# dps.net
KiCad netlist of a schematic drawn in EAGLE
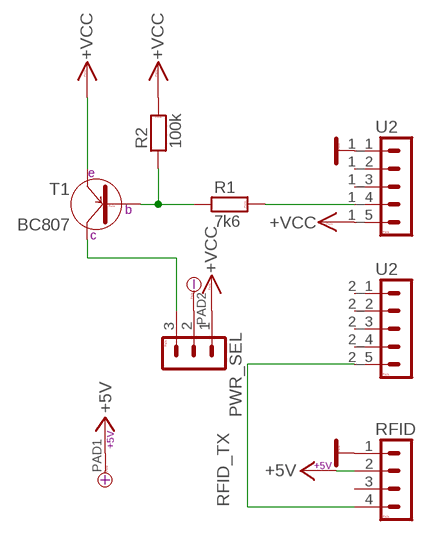
[diagram p0: schematic, sheet 1]

(export (version "E")
  (design (tool "Eeschema 10.0.6"))
  (components
    (comp (ref "PAD1")
      (value "+")
      (footprint "eagle-import:PAD_1")
      (libsource (lib "eagle-import") (part "PAD_1+"))
    )
    (comp (ref "PAD2")
      (value "-")
      (footprint "eagle-import:PAD_1")
      (libsource (lib "eagle-import") (part "PAD_1-"))
    )
    (comp (ref "PWR_SEL")
      (value "S1G3_JUMP")
      (footprint "eagle-import:S1G3_JUM")
      (libsource (lib "eagle-import") (part "S1G3_JUMP"))
    )
    (comp (ref "R1")
      (value "7k6")
      (footprint "eagle-import:1206")
      (libsource (lib "eagle-import") (part "R_SMD_1206"))
    )
    (comp (ref "R2")
      (value "100k")
      (footprint "eagle-import:1206")
      (libsource (lib "eagle-import") (part "R_SMD_1206"))
    )
    (comp (ref "RFID")
      (value "S1G4_JUMP")
      (footprint "eagle-import:S1G4_JUM")
      (libsource (lib "eagle-import") (part "S1G4_JUMP"))
    )
    (comp (ref "T1")
      (value "BC807")
      (footprint "eagle-import:SOT-23")
      (libsource (lib "eagle-import") (part "BC807"))
    )
    (comp (ref "U2")
      (value "S2G5_JUMP")
      (footprint "eagle-import:S2G5_JUM")
      (libsource (lib "eagle-import") (part "S2G5_JUMP"))
    )
  )
  (nets
    (net (code "1") (name "+5V") (class "Default")
      (node (ref "PAD1") (pin "1") (pinfunction "+_1") (pintype "passive"))
      (node (ref "RFID") (pin "2") (pinfunction "2_2") (pintype "passive"))
    )
    (net (code "2") (name "+VCC") (class "Default")
      (node (ref "PWR_SEL") (pin "1") (pinfunction "1_1") (pintype "passive"))
      (node (ref "R2") (pin "2") (pinfunction "2_2") (pintype "passive"))
      (node (ref "T1") (pin "2") (pinfunction "E_2") (pintype "passive"))
      (node (ref "U2") (pin "1_5") (pinfunction "5_1_5") (pintype "passive"))
    )
    (net (code "3") (name "/RFID_TX") (class "Default")
      (node (ref "RFID") (pin "4") (pinfunction "4_4") (pintype "passive"))
      (node (ref "U2") (pin "2_5") (pinfunction "5_2_5") (pintype "passive"))
    )
    (net (code "4") (name "GND") (class "Default")
      (node (ref "RFID") (pin "1") (pinfunction "1_1") (pintype "passive"))
      (node (ref "U2") (pin "1_1") (pinfunction "1_1_1") (pintype "passive"))
    )
    (net (code "5") (name "Net-(PAD2--)") (class "Default")
      (node (ref "PAD2") (pin "1") (pinfunction "-_1") (pintype "passive"))
      (node (ref "PWR_SEL") (pin "2") (pinfunction "2_2") (pintype "passive"))
    )
    (net (code "6") (name "Net-(T1-B)") (class "Default")
      (node (ref "R1") (pin "1") (pinfunction "1_1") (pintype "passive"))
      (node (ref "R2") (pin "1") (pinfunction "1_1") (pintype "passive"))
      (node (ref "T1") (pin "1") (pinfunction "B_1") (pintype "passive"))
    )
    (net (code "7") (name "Net-(T1-C)") (class "Default")
      (node (ref "PWR_SEL") (pin "3") (pinfunction "3_3") (pintype "passive"))
      (node (ref "T1") (pin "3") (pinfunction "C_3") (pintype "passive"))
    )
    (net (code "8") (name "Net-(U2A-4)") (class "Default")
      (node (ref "R1") (pin "2") (pinfunction "2_2") (pintype "passive"))
      (node (ref "U2") (pin "1_4") (pinfunction "4_1_4") (pintype "passive"))
    )
    (net (code "9") (name "unconnected-(RFID-Pad3)") (class "Default")
      (node (ref "RFID") (pin "3") (pinfunction "3_3") (pintype "passive"))
    )
    (net (code "10") (name "unconnected-(U2A-2-Pad1_2)") (class "Default")
      (node (ref "U2") (pin "1_2") (pinfunction "2_1_2") (pintype "passive"))
    )
    (net (code "11") (name "unconnected-(U2A-3-Pad1_3)") (class "Default")
      (node (ref "U2") (pin "1_3") (pinfunction "3_1_3") (pintype "passive"))
    )
    (net (code "12") (name "unconnected-(U2B-1-Pad2_1)") (class "Default")
      (node (ref "U2") (pin "2_1") (pinfunction "1_2_1") (pintype "passive"))
    )
    (net (code "13") (name "unconnected-(U2B-2-Pad2_2)") (class "Default")
      (node (ref "U2") (pin "2_2") (pinfunction "2_2_2") (pintype "passive"))
    )
    (net (code "14") (name "unconnected-(U2B-3-Pad2_3)") (class "Default")
      (node (ref "U2") (pin "2_3") (pinfunction "3_2_3") (pintype "passive"))
    )
    (net (code "15") (name "unconnected-(U2B-4-Pad2_4)") (class "Default")
      (node (ref "U2") (pin "2_4") (pinfunction "4_2_4") (pintype "passive"))
    )
  )
)
